# rpi_cm3plus_tablet.net
KiCad netlist of a schematic drawn in EAGLE
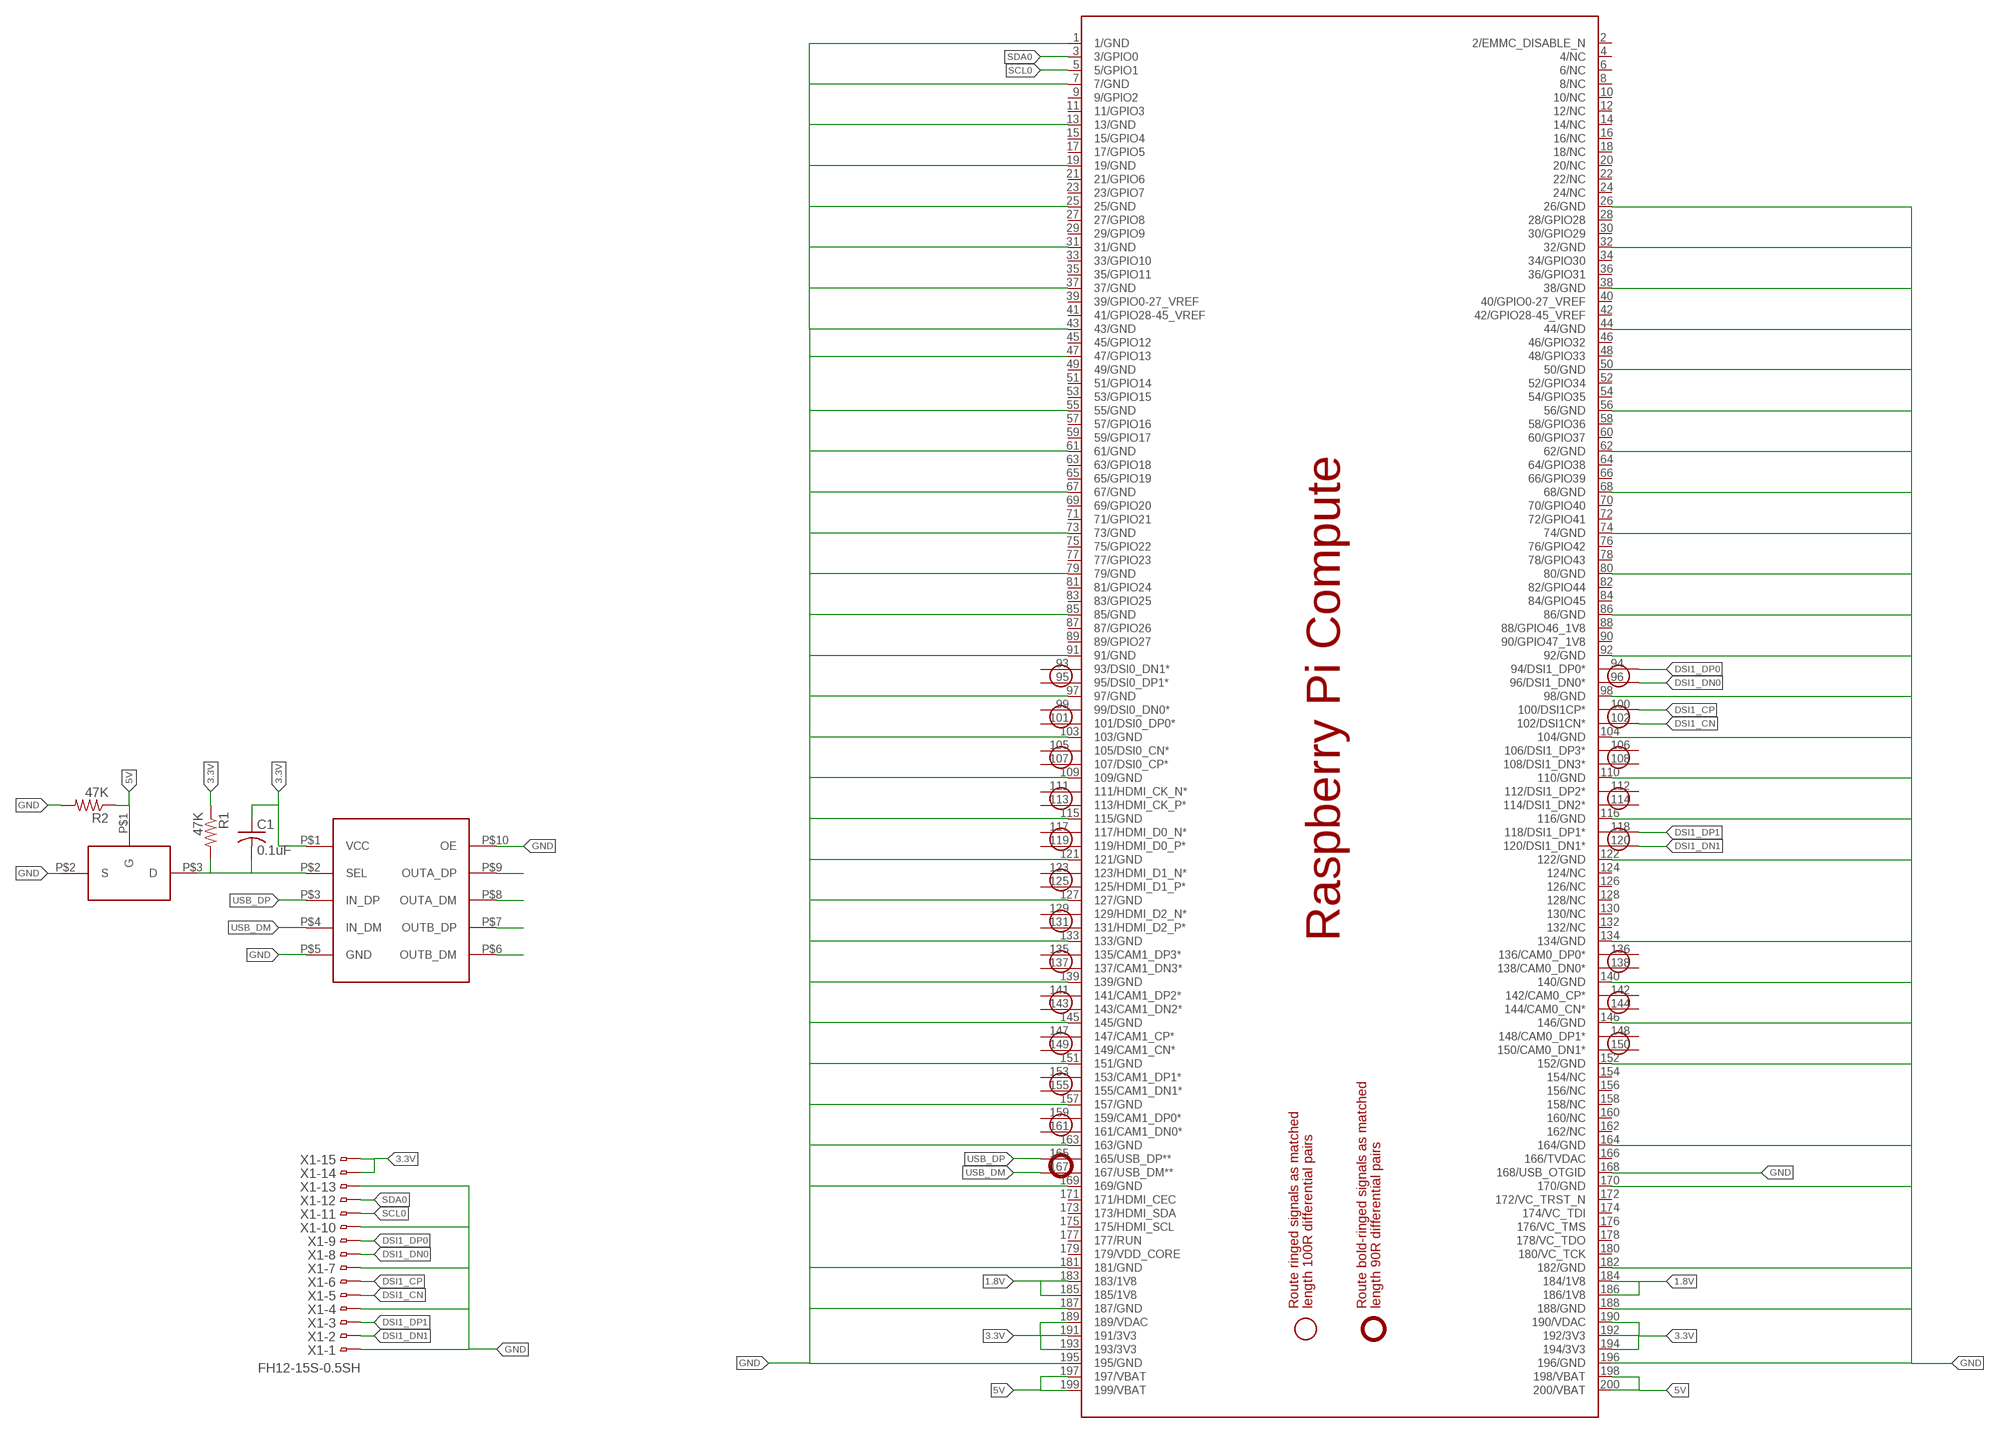
[diagram p0: schematic, sheet 1]

(export (version "E")
  (design (tool "Eeschema 10.0.6"))
  (components
    (comp (ref "C1")
      (value "0.1uF")
      (footprint "eagle-import:C0603K")
      (libsource (lib "eagle-import") (part "C-USC0603K"))
    )
    (comp (ref "PCB1")
      (value "RPI_COMPUTE")
      (footprint "eagle-import:RPI_COMPUTE")
      (libsource (lib "eagle-import") (part "RPI_COMPUTE"))
    )
    (comp (ref "R1")
      (value "47K")
      (footprint "eagle-import:R0603")
      (libsource (lib "eagle-import") (part "R-US_R0603"))
    )
    (comp (ref "R2")
      (value "47K")
      (footprint "eagle-import:R0603")
      (libsource (lib "eagle-import") (part "R-US_R0603"))
    )
    (comp (ref "U$1")
      (value "FSUSB42MUX")
      (footprint "eagle-import:MSOP-10")
      (libsource (lib "eagle-import") (part "FSUSB42MUX"))
    )
    (comp (ref "U$2")
      (value "BSS138N")
      (footprint "eagle-import:SOT-23")
      (libsource (lib "eagle-import") (part "BSS138N"))
    )
    (comp (ref "X1")
      (value "FH12-15S-0.5SH")
      (footprint "eagle-import:FH12-15S-0.5SH")
      (libsource (lib "eagle-import") (part "FH12-15S-0.5SH"))
    )
  )
  (nets
    (net (code "1") (name "1.8V") (class "Default")
      (node (ref "PCB1") (pin "183") (pinfunction "183/1V8_183") (pintype "bidirectional"))
      (node (ref "PCB1") (pin "184") (pinfunction "184/1V8_184") (pintype "bidirectional"))
      (node (ref "PCB1") (pin "185") (pinfunction "185/1V8_185") (pintype "bidirectional"))
      (node (ref "PCB1") (pin "186") (pinfunction "186/1V8_186") (pintype "bidirectional"))
    )
    (net (code "2") (name "3.3V") (class "Default")
      (node (ref "C1") (pin "1") (pinfunction "1_1") (pintype "passive"))
      (node (ref "PCB1") (pin "189") (pinfunction "189/VDAC_189") (pintype "bidirectional"))
      (node (ref "PCB1") (pin "190") (pinfunction "190/VDAC_190") (pintype "bidirectional"))
      (node (ref "PCB1") (pin "191") (pinfunction "191/3V3_191") (pintype "bidirectional"))
      (node (ref "PCB1") (pin "192") (pinfunction "192/3V3_192") (pintype "bidirectional"))
      (node (ref "PCB1") (pin "193") (pinfunction "193/3V3_193") (pintype "bidirectional"))
      (node (ref "PCB1") (pin "194") (pinfunction "194/3V3_194") (pintype "bidirectional"))
      (node (ref "R1") (pin "1") (pinfunction "1_1") (pintype "passive"))
      (node (ref "U$1") (pin "P$1") (pinfunction "VCC_P$1") (pintype "bidirectional"))
      (node (ref "X1") (pin "14") (pinfunction "1_14") (pintype "passive"))
      (node (ref "X1") (pin "15") (pinfunction "1_15") (pintype "passive"))
    )
    (net (code "3") (name "5V") (class "Default")
      (node (ref "PCB1") (pin "197") (pinfunction "197/VBAT_197") (pintype "bidirectional"))
      (node (ref "PCB1") (pin "198") (pinfunction "198/VBAT_198") (pintype "bidirectional"))
      (node (ref "PCB1") (pin "199") (pinfunction "199/VBAT_199") (pintype "bidirectional"))
      (node (ref "PCB1") (pin "200") (pinfunction "200/VBAT_200") (pintype "bidirectional"))
      (node (ref "R2") (pin "1") (pinfunction "1_1") (pintype "passive"))
      (node (ref "U$2") (pin "P$1") (pinfunction "G_P$1") (pintype "bidirectional"))
    )
    (net (code "4") (name "DSI1_CN") (class "Default")
      (node (ref "PCB1") (pin "102") (pinfunction "102/DSI1CN*_102") (pintype "bidirectional"))
      (node (ref "X1") (pin "5") (pinfunction "1_5") (pintype "passive"))
    )
    (net (code "5") (name "DSI1_CP") (class "Default")
      (node (ref "PCB1") (pin "100") (pinfunction "100/DSI1CP*_100") (pintype "bidirectional"))
      (node (ref "X1") (pin "6") (pinfunction "1_6") (pintype "passive"))
    )
    (net (code "6") (name "DSI1_DN0") (class "Default")
      (node (ref "PCB1") (pin "96") (pinfunction "96/DSI1_DN0*_96") (pintype "bidirectional"))
      (node (ref "X1") (pin "8") (pinfunction "1_8") (pintype "passive"))
    )
    (net (code "7") (name "DSI1_DN1") (class "Default")
      (node (ref "PCB1") (pin "120") (pinfunction "120/DSI1_DN1*_120") (pintype "bidirectional"))
      (node (ref "X1") (pin "2") (pinfunction "1_2") (pintype "passive"))
    )
    (net (code "8") (name "DSI1_DP0") (class "Default")
      (node (ref "PCB1") (pin "94") (pinfunction "94/DSI1_DP0*_94") (pintype "bidirectional"))
      (node (ref "X1") (pin "9") (pinfunction "1_9") (pintype "passive"))
    )
    (net (code "9") (name "DSI1_DP1") (class "Default")
      (node (ref "PCB1") (pin "118") (pinfunction "118/DSI1_DP1*_118") (pintype "bidirectional"))
      (node (ref "X1") (pin "3") (pinfunction "1_3") (pintype "passive"))
    )
    (net (code "10") (name "GND") (class "Default")
      (node (ref "PCB1") (pin "1") (pinfunction "1/GND_1") (pintype "bidirectional"))
      (node (ref "PCB1") (pin "103") (pinfunction "103/GND_103") (pintype "bidirectional"))
      (node (ref "PCB1") (pin "104") (pinfunction "104/GND_104") (pintype "bidirectional"))
      (node (ref "PCB1") (pin "109") (pinfunction "109/GND_109") (pintype "bidirectional"))
      (node (ref "PCB1") (pin "110") (pinfunction "110/GND_110") (pintype "bidirectional"))
      (node (ref "PCB1") (pin "115") (pinfunction "115/GND_115") (pintype "bidirectional"))
      (node (ref "PCB1") (pin "116") (pinfunction "116/GND_116") (pintype "bidirectional"))
      (node (ref "PCB1") (pin "121") (pinfunction "121/GND_121") (pintype "bidirectional"))
      (node (ref "PCB1") (pin "122") (pinfunction "122/GND_122") (pintype "bidirectional"))
      (node (ref "PCB1") (pin "127") (pinfunction "127/GND_127") (pintype "bidirectional"))
      (node (ref "PCB1") (pin "13") (pinfunction "13/GND_13") (pintype "bidirectional"))
      (node (ref "PCB1") (pin "133") (pinfunction "133/GND_133") (pintype "bidirectional"))
      (node (ref "PCB1") (pin "134") (pinfunction "134/GND_134") (pintype "bidirectional"))
      (node (ref "PCB1") (pin "139") (pinfunction "139/GND_139") (pintype "bidirectional"))
      (node (ref "PCB1") (pin "140") (pinfunction "140/GND_140") (pintype "bidirectional"))
      (node (ref "PCB1") (pin "145") (pinfunction "145/GND_145") (pintype "bidirectional"))
      (node (ref "PCB1") (pin "146") (pinfunction "146/GND_146") (pintype "bidirectional"))
      (node (ref "PCB1") (pin "151") (pinfunction "151/GND_151") (pintype "bidirectional"))
      (node (ref "PCB1") (pin "152") (pinfunction "152/GND_152") (pintype "bidirectional"))
      (node (ref "PCB1") (pin "157") (pinfunction "157/GND_157") (pintype "bidirectional"))
      (node (ref "PCB1") (pin "163") (pinfunction "163/GND_163") (pintype "bidirectional"))
      (node (ref "PCB1") (pin "164") (pinfunction "164/GND_164") (pintype "bidirectional"))
      (node (ref "PCB1") (pin "168") (pinfunction "168/USB_OTGID_168") (pintype "bidirectional"))
      (node (ref "PCB1") (pin "169") (pinfunction "169/GND_169") (pintype "bidirectional"))
      (node (ref "PCB1") (pin "170") (pinfunction "170/GND_170") (pintype "bidirectional"))
      (node (ref "PCB1") (pin "181") (pinfunction "181/GND_181") (pintype "bidirectional"))
      (node (ref "PCB1") (pin "182") (pinfunction "182/GND_182") (pintype "bidirectional"))
      (node (ref "PCB1") (pin "187") (pinfunction "187/GND_187") (pintype "bidirectional"))
      (node (ref "PCB1") (pin "188") (pinfunction "188/GND_188") (pintype "bidirectional"))
      (node (ref "PCB1") (pin "19") (pinfunction "19/GND_19") (pintype "bidirectional"))
      (node (ref "PCB1") (pin "195") (pinfunction "195/GND_195") (pintype "bidirectional"))
      (node (ref "PCB1") (pin "196") (pinfunction "196/GND_196") (pintype "bidirectional"))
      (node (ref "PCB1") (pin "25") (pinfunction "25/GND_25") (pintype "bidirectional"))
      (node (ref "PCB1") (pin "26") (pinfunction "26/GND_26") (pintype "bidirectional"))
      (node (ref "PCB1") (pin "31") (pinfunction "31/GND_31") (pintype "bidirectional"))
      (node (ref "PCB1") (pin "32") (pinfunction "32/GND_32") (pintype "bidirectional"))
      (node (ref "PCB1") (pin "37") (pinfunction "37/GND_37") (pintype "bidirectional"))
      (node (ref "PCB1") (pin "38") (pinfunction "38/GND_38") (pintype "bidirectional"))
      (node (ref "PCB1") (pin "43") (pinfunction "43/GND_43") (pintype "bidirectional"))
      (node (ref "PCB1") (pin "44") (pinfunction "44/GND_44") (pintype "bidirectional"))
      (node (ref "PCB1") (pin "47") (pinfunction "47/GPIO13_47") (pintype "bidirectional"))
      (node (ref "PCB1") (pin "50") (pinfunction "50/GND_50") (pintype "bidirectional"))
      (node (ref "PCB1") (pin "55") (pinfunction "55/GND_55") (pintype "bidirectional"))
      (node (ref "PCB1") (pin "56") (pinfunction "56/GND_56") (pintype "bidirectional"))
      (node (ref "PCB1") (pin "61") (pinfunction "61/GND_61") (pintype "bidirectional"))
      (node (ref "PCB1") (pin "62") (pinfunction "62/GND_62") (pintype "bidirectional"))
      (node (ref "PCB1") (pin "67") (pinfunction "67/GND_67") (pintype "bidirectional"))
      (node (ref "PCB1") (pin "68") (pinfunction "68/GND_68") (pintype "bidirectional"))
      (node (ref "PCB1") (pin "7") (pinfunction "7/GND_7") (pintype "bidirectional"))
      (node (ref "PCB1") (pin "73") (pinfunction "73/GND_73") (pintype "bidirectional"))
      (node (ref "PCB1") (pin "74") (pinfunction "74/GND_74") (pintype "bidirectional"))
      (node (ref "PCB1") (pin "79") (pinfunction "79/GND_79") (pintype "bidirectional"))
      (node (ref "PCB1") (pin "80") (pinfunction "80/GND_80") (pintype "bidirectional"))
      (node (ref "PCB1") (pin "85") (pinfunction "85/GND_85") (pintype "bidirectional"))
      (node (ref "PCB1") (pin "86") (pinfunction "86/GND_86") (pintype "bidirectional"))
      (node (ref "PCB1") (pin "91") (pinfunction "91/GND_91") (pintype "bidirectional"))
      (node (ref "PCB1") (pin "92") (pinfunction "92/GND_92") (pintype "bidirectional"))
      (node (ref "PCB1") (pin "97") (pinfunction "97/GND_97") (pintype "bidirectional"))
      (node (ref "PCB1") (pin "98") (pinfunction "98/GND_98") (pintype "bidirectional"))
      (node (ref "R2") (pin "2") (pinfunction "2_2") (pintype "passive"))
      (node (ref "U$1") (pin "P$10") (pinfunction "OE_P$10") (pintype "bidirectional"))
      (node (ref "U$1") (pin "P$5") (pinfunction "GND_P$5") (pintype "bidirectional"))
      (node (ref "U$2") (pin "P$2") (pinfunction "S_P$2") (pintype "bidirectional"))
      (node (ref "X1") (pin "1") (pinfunction "1_1") (pintype "passive"))
      (node (ref "X1") (pin "10") (pinfunction "1_10") (pintype "passive"))
      (node (ref "X1") (pin "13") (pinfunction "1_13") (pintype "passive"))
      (node (ref "X1") (pin "4") (pinfunction "1_4") (pintype "passive"))
      (node (ref "X1") (pin "7") (pinfunction "1_7") (pintype "passive"))
    )
    (net (code "11") (name "Net-(U$1-SEL)") (class "Default")
      (node (ref "C1") (pin "2") (pinfunction "2_2") (pintype "passive"))
      (node (ref "R1") (pin "2") (pinfunction "2_2") (pintype "passive"))
      (node (ref "U$1") (pin "P$2") (pinfunction "SEL_P$2") (pintype "bidirectional"))
      (node (ref "U$2") (pin "P$3") (pinfunction "D_P$3") (pintype "bidirectional"))
    )
    (net (code "12") (name "SCL0") (class "Default")
      (node (ref "PCB1") (pin "5") (pinfunction "5/GPIO1_5") (pintype "bidirectional"))
      (node (ref "X1") (pin "11") (pinfunction "1_11") (pintype "passive"))
    )
    (net (code "13") (name "SDA0") (class "Default")
      (node (ref "PCB1") (pin "3") (pinfunction "3/GPIO0_3") (pintype "bidirectional"))
      (node (ref "X1") (pin "12") (pinfunction "1_12") (pintype "passive"))
    )
    (net (code "14") (name "USB_DM") (class "Default")
      (node (ref "PCB1") (pin "167") (pinfunction "167/USB_DM**_167") (pintype "bidirectional"))
      (node (ref "U$1") (pin "P$4") (pinfunction "IN_DM_P$4") (pintype "bidirectional"))
    )
    (net (code "15") (name "USB_DP") (class "Default")
      (node (ref "PCB1") (pin "165") (pinfunction "165/USB_DP**_165") (pintype "bidirectional"))
      (node (ref "U$1") (pin "P$3") (pinfunction "IN_DP_P$3") (pintype "bidirectional"))
    )
    (net (code "16") (name "unconnected-(PCB1-2{slash}EMMC_DISABLE_N-Pad2)") (class "Default")
      (node (ref "PCB1") (pin "2") (pinfunction "2/EMMC_DISABLE_N_2") (pintype "bidirectional"))
    )
    (net (code "17") (name "unconnected-(PCB1-4{slash}NC-Pad4)") (class "Default")
      (node (ref "PCB1") (pin "4") (pinfunction "4/NC_4") (pintype "bidirectional"))
    )
    (net (code "18") (name "unconnected-(PCB1-6{slash}NC-Pad6)") (class "Default")
      (node (ref "PCB1") (pin "6") (pinfunction "6/NC_6") (pintype "bidirectional"))
    )
    (net (code "19") (name "unconnected-(PCB1-8{slash}NC-Pad8)") (class "Default")
      (node (ref "PCB1") (pin "8") (pinfunction "8/NC_8") (pintype "bidirectional"))
    )
    (net (code "20") (name "unconnected-(PCB1-9{slash}GPIO2-Pad9)") (class "Default")
      (node (ref "PCB1") (pin "9") (pinfunction "9/GPIO2_9") (pintype "bidirectional"))
    )
    (net (code "21") (name "unconnected-(PCB1-10{slash}NC-Pad10)") (class "Default")
      (node (ref "PCB1") (pin "10") (pinfunction "10/NC_10") (pintype "bidirectional"))
    )
    (net (code "22") (name "unconnected-(PCB1-11{slash}GPIO3-Pad11)") (class "Default")
      (node (ref "PCB1") (pin "11") (pinfunction "11/GPIO3_11") (pintype "bidirectional"))
    )
    (net (code "23") (name "unconnected-(PCB1-12{slash}NC-Pad12)") (class "Default")
      (node (ref "PCB1") (pin "12") (pinfunction "12/NC_12") (pintype "bidirectional"))
    )
    (net (code "24") (name "unconnected-(PCB1-14{slash}NC-Pad14)") (class "Default")
      (node (ref "PCB1") (pin "14") (pinfunction "14/NC_14") (pintype "bidirectional"))
    )
    (net (code "25") (name "unconnected-(PCB1-15{slash}GPIO4-Pad15)") (class "Default")
      (node (ref "PCB1") (pin "15") (pinfunction "15/GPIO4_15") (pintype "bidirectional"))
    )
    (net (code "26") (name "unconnected-(PCB1-16{slash}NC-Pad16)") (class "Default")
      (node (ref "PCB1") (pin "16") (pinfunction "16/NC_16") (pintype "bidirectional"))
    )
    (net (code "27") (name "unconnected-(PCB1-17{slash}GPIO5-Pad17)") (class "Default")
      (node (ref "PCB1") (pin "17") (pinfunction "17/GPIO5_17") (pintype "bidirectional"))
    )
    (net (code "28") (name "unconnected-(PCB1-18{slash}NC-Pad18)") (class "Default")
      (node (ref "PCB1") (pin "18") (pinfunction "18/NC_18") (pintype "bidirectional"))
    )
    (net (code "29") (name "unconnected-(PCB1-20{slash}NC-Pad20)") (class "Default")
      (node (ref "PCB1") (pin "20") (pinfunction "20/NC_20") (pintype "bidirectional"))
    )
    (net (code "30") (name "unconnected-(PCB1-21{slash}GPIO6-Pad21)") (class "Default")
      (node (ref "PCB1") (pin "21") (pinfunction "21/GPIO6_21") (pintype "bidirectional"))
    )
    (net (code "31") (name "unconnected-(PCB1-22{slash}NC-Pad22)") (class "Default")
      (node (ref "PCB1") (pin "22") (pinfunction "22/NC_22") (pintype "bidirectional"))
    )
    (net (code "32") (name "unconnected-(PCB1-23{slash}GPIO7-Pad23)") (class "Default")
      (node (ref "PCB1") (pin "23") (pinfunction "23/GPIO7_23") (pintype "bidirectional"))
    )
    (net (code "33") (name "unconnected-(PCB1-24{slash}NC-Pad24)") (class "Default")
      (node (ref "PCB1") (pin "24") (pinfunction "24/NC_24") (pintype "bidirectional"))
    )
    (net (code "34") (name "unconnected-(PCB1-27{slash}GPIO8-Pad27)") (class "Default")
      (node (ref "PCB1") (pin "27") (pinfunction "27/GPIO8_27") (pintype "bidirectional"))
    )
    (net (code "35") (name "unconnected-(PCB1-28{slash}GPIO28-Pad28)") (class "Default")
      (node (ref "PCB1") (pin "28") (pinfunction "28/GPIO28_28") (pintype "bidirectional"))
    )
    (net (code "36") (name "unconnected-(PCB1-29{slash}GPIO9-Pad29)") (class "Default")
      (node (ref "PCB1") (pin "29") (pinfunction "29/GPIO9_29") (pintype "bidirectional"))
    )
    (net (code "37") (name "unconnected-(PCB1-30{slash}GPIO29-Pad30)") (class "Default")
      (node (ref "PCB1") (pin "30") (pinfunction "30/GPIO29_30") (pintype "bidirectional"))
    )
    (net (code "38") (name "unconnected-(PCB1-33{slash}GPIO10-Pad33)") (class "Default")
      (node (ref "PCB1") (pin "33") (pinfunction "33/GPIO10_33") (pintype "bidirectional"))
    )
    (net (code "39") (name "unconnected-(PCB1-34{slash}GPIO30-Pad34)") (class "Default")
      (node (ref "PCB1") (pin "34") (pinfunction "34/GPIO30_34") (pintype "bidirectional"))
    )
    (net (code "40") (name "unconnected-(PCB1-35{slash}GPIO11-Pad35)") (class "Default")
      (node (ref "PCB1") (pin "35") (pinfunction "35/GPIO11_35") (pintype "bidirectional"))
    )
    (net (code "41") (name "unconnected-(PCB1-36{slash}GPIO31-Pad36)") (class "Default")
      (node (ref "PCB1") (pin "36") (pinfunction "36/GPIO31_36") (pintype "bidirectional"))
    )
    (net (code "42") (name "unconnected-(PCB1-39{slash}GPIO0-27_VREF-Pad39)") (class "Default")
      (node (ref "PCB1") (pin "39") (pinfunction "39/GPIO0-27_VREF_39") (pintype "bidirectional"))
    )
    (net (code "43") (name "unconnected-(PCB1-40{slash}GPIO0-27_VREF-Pad40)") (class "Default")
      (node (ref "PCB1") (pin "40") (pinfunction "40/GPIO0-27_VREF_40") (pintype "bidirectional"))
    )
    (net (code "44") (name "unconnected-(PCB1-41{slash}GPIO28-45_VREF-Pad41)") (class "Default")
      (node (ref "PCB1") (pin "41") (pinfunction "41/GPIO28-45_VREF_41") (pintype "bidirectional"))
    )
    (net (code "45") (name "unconnected-(PCB1-42{slash}GPIO28-45_VREF-Pad42)") (class "Default")
      (node (ref "PCB1") (pin "42") (pinfunction "42/GPIO28-45_VREF_42") (pintype "bidirectional"))
    )
    (net (code "46") (name "unconnected-(PCB1-45{slash}GPIO12-Pad45)") (class "Default")
      (node (ref "PCB1") (pin "45") (pinfunction "45/GPIO12_45") (pintype "bidirectional"))
    )
    (net (code "47") (name "unconnected-(PCB1-46{slash}GPIO32-Pad46)") (class "Default")
      (node (ref "PCB1") (pin "46") (pinfunction "46/GPIO32_46") (pintype "bidirectional"))
    )
    (net (code "48") (name "unconnected-(PCB1-48{slash}GPIO33-Pad48)") (class "Default")
      (node (ref "PCB1") (pin "48") (pinfunction "48/GPIO33_48") (pintype "bidirectional"))
    )
    (net (code "49") (name "unconnected-(PCB1-49{slash}GND-Pad49)") (class "Default")
      (node (ref "PCB1") (pin "49") (pinfunction "49/GND_49") (pintype "bidirectional"))
    )
    (net (code "50") (name "unconnected-(PCB1-51{slash}GPIO14-Pad51)") (class "Default")
      (node (ref "PCB1") (pin "51") (pinfunction "51/GPIO14_51") (pintype "bidirectional"))
    )
    (net (code "51") (name "unconnected-(PCB1-52{slash}GPIO34-Pad52)") (class "Default")
      (node (ref "PCB1") (pin "52") (pinfunction "52/GPIO34_52") (pintype "bidirectional"))
    )
    (net (code "52") (name "unconnected-(PCB1-53{slash}GPIO15-Pad53)") (class "Default")
      (node (ref "PCB1") (pin "53") (pinfunction "53/GPIO15_53") (pintype "bidirectional"))
    )
    (net (code "53") (name "unconnected-(PCB1-54{slash}GPIO35-Pad54)") (class "Default")
      (node (ref "PCB1") (pin "54") (pinfunction "54/GPIO35_54") (pintype "bidirectional"))
    )
    (net (code "54") (name "unconnected-(PCB1-57{slash}GPIO16-Pad57)") (class "Default")
      (node (ref "PCB1") (pin "57") (pinfunction "57/GPIO16_57") (pintype "bidirectional"))
    )
    (net (code "55") (name "unconnected-(PCB1-58{slash}GPIO36-Pad58)") (class "Default")
      (node (ref "PCB1") (pin "58") (pinfunction "58/GPIO36_58") (pintype "bidirectional"))
    )
    (net (code "56") (name "unconnected-(PCB1-59{slash}GPIO17-Pad59)") (class "Default")
      (node (ref "PCB1") (pin "59") (pinfunction "59/GPIO17_59") (pintype "bidirectional"))
    )
    (net (code "57") (name "unconnected-(PCB1-60{slash}GPIO37-Pad60)") (class "Default")
      (node (ref "PCB1") (pin "60") (pinfunction "60/GPIO37_60") (pintype "bidirectional"))
    )
    (net (code "58") (name "unconnected-(PCB1-63{slash}GPIO18-Pad63)") (class "Default")
      (node (ref "PCB1") (pin "63") (pinfunction "63/GPIO18_63") (pintype "bidirectional"))
    )
    (net (code "59") (name "unconnected-(PCB1-64{slash}GPIO38-Pad64)") (class "Default")
      (node (ref "PCB1") (pin "64") (pinfunction "64/GPIO38_64") (pintype "bidirectional"))
    )
    (net (code "60") (name "unconnected-(PCB1-65{slash}GPIO19-Pad65)") (class "Default")
      (node (ref "PCB1") (pin "65") (pinfunction "65/GPIO19_65") (pintype "bidirectional"))
    )
    (net (code "61") (name "unconnected-(PCB1-66{slash}GPIO39-Pad66)") (class "Default")
      (node (ref "PCB1") (pin "66") (pinfunction "66/GPIO39_66") (pintype "bidirectional"))
    )
    (net (code "62") (name "unconnected-(PCB1-69{slash}GPIO20-Pad69)") (class "Default")
      (node (ref "PCB1") (pin "69") (pinfunction "69/GPIO20_69") (pintype "bidirectional"))
    )
    (net (code "63") (name "unconnected-(PCB1-70{slash}GPIO40-Pad70)") (class "Default")
      (node (ref "PCB1") (pin "70") (pinfunction "70/GPIO40_70") (pintype "bidirectional"))
    )
    (net (code "64") (name "unconnected-(PCB1-71{slash}GPIO21-Pad71)") (class "Default")
      (node (ref "PCB1") (pin "71") (pinfunction "71/GPIO21_71") (pintype "bidirectional"))
    )
    (net (code "65") (name "unconnected-(PCB1-72{slash}GPIO41-Pad72)") (class "Default")
      (node (ref "PCB1") (pin "72") (pinfunction "72/GPIO41_72") (pintype "bidirectional"))
    )
    (net (code "66") (name "unconnected-(PCB1-75{slash}GPIO22-Pad75)") (class "Default")
      (node (ref "PCB1") (pin "75") (pinfunction "75/GPIO22_75") (pintype "bidirectional"))
    )
    (net (code "67") (name "unconnected-(PCB1-76{slash}GPIO42-Pad76)") (class "Default")
      (node (ref "PCB1") (pin "76") (pinfunction "76/GPIO42_76") (pintype "bidirectional"))
    )
    (net (code "68") (name "unconnected-(PCB1-77{slash}GPIO23-Pad77)") (class "Default")
      (node (ref "PCB1") (pin "77") (pinfunction "77/GPIO23_77") (pintype "bidirectional"))
    )
    (net (code "69") (name "unconnected-(PCB1-78{slash}GPIO43-Pad78)") (class "Default")
      (node (ref "PCB1") (pin "78") (pinfunction "78/GPIO43_78") (pintype "bidirectional"))
    )
    (net (code "70") (name "unconnected-(PCB1-81{slash}GPIO24-Pad81)") (class "Default")
      (node (ref "PCB1") (pin "81") (pinfunction "81/GPIO24_81") (pintype "bidirectional"))
    )
    (net (code "71") (name "unconnected-(PCB1-82{slash}GPIO44-Pad82)") (class "Default")
      (node (ref "PCB1") (pin "82") (pinfunction "82/GPIO44_82") (pintype "bidirectional"))
    )
    (net (code "72") (name "unconnected-(PCB1-83{slash}GPIO25-Pad83)") (class "Default")
      (node (ref "PCB1") (pin "83") (pinfunction "83/GPIO25_83") (pintype "bidirectional"))
    )
    (net (code "73") (name "unconnected-(PCB1-84{slash}GPIO45-Pad84)") (class "Default")
      (node (ref "PCB1") (pin "84") (pinfunction "84/GPIO45_84") (pintype "bidirectional"))
    )
    (net (code "74") (name "unconnected-(PCB1-87{slash}GPIO26-Pad87)") (class "Default")
      (node (ref "PCB1") (pin "87") (pinfunction "87/GPIO26_87") (pintype "bidirectional"))
    )
    (net (code "75") (name "unconnected-(PCB1-88{slash}GPIO46_1V8-Pad88)") (class "Default")
      (node (ref "PCB1") (pin "88") (pinfunction "88/GPIO46_1V8_88") (pintype "bidirectional"))
    )
    (net (code "76") (name "unconnected-(PCB1-89{slash}GPIO27-Pad89)") (class "Default")
      (node (ref "PCB1") (pin "89") (pinfunction "89/GPIO27_89") (pintype "bidirectional"))
    )
    (net (code "77") (name "unconnected-(PCB1-90{slash}GPIO47_1V8-Pad90)") (class "Default")
      (node (ref "PCB1") (pin "90") (pinfunction "90/GPIO47_1V8_90") (pintype "bidirectional"))
    )
    (net (code "78") (name "unconnected-(PCB1-93{slash}DSI0_DN1*-Pad93)") (class "Default")
      (node (ref "PCB1") (pin "93") (pinfunction "93/DSI0_DN1*_93") (pintype "bidirectional"))
    )
    (net (code "79") (name "unconnected-(PCB1-95{slash}DSI0_DP1*-Pad95)") (class "Default")
      (node (ref "PCB1") (pin "95") (pinfunction "95/DSI0_DP1*_95") (pintype "bidirectional"))
    )
    (net (code "80") (name "unconnected-(PCB1-99{slash}DSI0_DN0*-Pad99)") (class "Default")
      (node (ref "PCB1") (pin "99") (pinfunction "99/DSI0_DN0*_99") (pintype "bidirectional"))
    )
    (net (code "81") (name "unconnected-(PCB1-101{slash}DSI0_DP0*-Pad101)") (class "Default")
      (node (ref "PCB1") (pin "101") (pinfunction "101/DSI0_DP0*_101") (pintype "bidirectional"))
    )
    (net (code "82") (name "unconnected-(PCB1-105{slash}DSI0_CN*-Pad105)") (class "Default")
      (node (ref "PCB1") (pin "105") (pinfunction "105/DSI0_CN*_105") (pintype "bidirectional"))
    )
    (net (code "83") (name "unconnected-(PCB1-106{slash}DSI1_DP3*-Pad106)") (class "Default")
      (node (ref "PCB1") (pin "106") (pinfunction "106/DSI1_DP3*_106") (pintype "bidirectional"))
    )
    (net (code "84") (name "unconnected-(PCB1-107{slash}DSI0_CP*-Pad107)") (class "Default")
      (node (ref "PCB1") (pin "107") (pinfunction "107/DSI0_CP*_107") (pintype "bidirectional"))
    )
    (net (code "85") (name "unconnected-(PCB1-108{slash}DSI1_DN3*-Pad108)") (class "Default")
      (node (ref "PCB1") (pin "108") (pinfunction "108/DSI1_DN3*_108") (pintype "bidirectional"))
    )
    (net (code "86") (name "unconnected-(PCB1-111{slash}HDMI_CK_N*-Pad111)") (class "Default")
      (node (ref "PCB1") (pin "111") (pinfunction "111/HDMI_CK_N*_111") (pintype "bidirectional"))
    )
    (net (code "87") (name "unconnected-(PCB1-112{slash}DSI1_DP2*-Pad112)") (class "Default")
      (node (ref "PCB1") (pin "112") (pinfunction "112/DSI1_DP2*_112") (pintype "bidirectional"))
    )
    (net (code "88") (name "unconnected-(PCB1-113{slash}HDMI_CK_P*-Pad113)") (class "Default")
      (node (ref "PCB1") (pin "113") (pinfunction "113/HDMI_CK_P*_113") (pintype "bidirectional"))
    )
    (net (code "89") (name "unconnected-(PCB1-114{slash}DSI1_DN2*-Pad114)") (class "Default")
      (node (ref "PCB1") (pin "114") (pinfunction "114/DSI1_DN2*_114") (pintype "bidirectional"))
    )
    (net (code "90") (name "unconnected-(PCB1-117{slash}HDMI_D0_N*-Pad117)") (class "Default")
      (node (ref "PCB1") (pin "117") (pinfunction "117/HDMI_D0_N*_117") (pintype "bidirectional"))
    )
    (net (code "91") (name "unconnected-(PCB1-119{slash}HDMI_D0_P*-Pad119)") (class "Default")
      (node (ref "PCB1") (pin "119") (pinfunction "119/HDMI_D0_P*_119") (pintype "bidirectional"))
    )
    (net (code "92") (name "unconnected-(PCB1-123{slash}HDMI_D1_N*-Pad123)") (class "Default")
      (node (ref "PCB1") (pin "123") (pinfunction "123/HDMI_D1_N*_123") (pintype "bidirectional"))
    )
    (net (code "93") (name "unconnected-(PCB1-124{slash}NC-Pad124)") (class "Default")
      (node (ref "PCB1") (pin "124") (pinfunction "124/NC_124") (pintype "bidirectional"))
    )
    (net (code "94") (name "unconnected-(PCB1-125{slash}HDMI_D1_P*-Pad125)") (class "Default")
      (node (ref "PCB1") (pin "125") (pinfunction "125/HDMI_D1_P*_125") (pintype "bidirectional"))
    )
    (net (code "95") (name "unconnected-(PCB1-126{slash}NC-Pad126)") (class "Default")
      (node (ref "PCB1") (pin "126") (pinfunction "126/NC_126") (pintype "bidirectional"))
    )
    (net (code "96") (name "unconnected-(PCB1-128{slash}NC-Pad128)") (class "Default")
      (node (ref "PCB1") (pin "128") (pinfunction "128/NC_128") (pintype "bidirectional"))
    )
    (net (code "97") (name "unconnected-(PCB1-129{slash}HDMI_D2_N*-Pad129)") (class "Default")
      (node (ref "PCB1") (pin "129") (pinfunction "129/HDMI_D2_N*_129") (pintype "bidirectional"))
    )
    (net (code "98") (name "unconnected-(PCB1-130{slash}NC-Pad130)") (class "Default")
      (node (ref "PCB1") (pin "130") (pinfunction "130/NC_130") (pintype "bidirectional"))
    )
    (net (code "99") (name "unconnected-(PCB1-131{slash}HDMI_D2_P*-Pad131)") (class "Default")
      (node (ref "PCB1") (pin "131") (pinfunction "131/HDMI_D2_P*_131") (pintype "bidirectional"))
    )
    (net (code "100") (name "unconnected-(PCB1-132{slash}NC-Pad132)") (class "Default")
      (node (ref "PCB1") (pin "132") (pinfunction "132/NC_132") (pintype "bidirectional"))
    )
    (net (code "101") (name "unconnected-(PCB1-135{slash}CAM1_DP3*-Pad135)") (class "Default")
      (node (ref "PCB1") (pin "135") (pinfunction "135/CAM1_DP3*_135") (pintype "bidirectional"))
    )
    (net (code "102") (name "unconnected-(PCB1-136{slash}CAM0_DP0*-Pad136)") (class "Default")
      (node (ref "PCB1") (pin "136") (pinfunction "136/CAM0_DP0*_136") (pintype "bidirectional"))
    )
    (net (code "103") (name "unconnected-(PCB1-137{slash}CAM1_DN3*-Pad137)") (class "Default")
      (node (ref "PCB1") (pin "137") (pinfunction "137/CAM1_DN3*_137") (pintype "bidirectional"))
    )
    (net (code "104") (name "unconnected-(PCB1-138{slash}CAM0_DN0*-Pad138)") (class "Default")
      (node (ref "PCB1") (pin "138") (pinfunction "138/CAM0_DN0*_138") (pintype "bidirectional"))
    )
    (net (code "105") (name "unconnected-(PCB1-141{slash}CAM1_DP2*-Pad141)") (class "Default")
      (node (ref "PCB1") (pin "141") (pinfunction "141/CAM1_DP2*_141") (pintype "bidirectional"))
    )
    (net (code "106") (name "unconnected-(PCB1-142{slash}CAM0_CP*-Pad142)") (class "Default")
      (node (ref "PCB1") (pin "142") (pinfunction "142/CAM0_CP*_142") (pintype "bidirectional"))
    )
    (net (code "107") (name "unconnected-(PCB1-143{slash}CAM1_DN2*-Pad143)") (class "Default")
      (node (ref "PCB1") (pin "143") (pinfunction "143/CAM1_DN2*_143") (pintype "bidirectional"))
    )
    (net (code "108") (name "unconnected-(PCB1-144{slash}CAM0_CN*-Pad144)") (class "Default")
      (node (ref "PCB1") (pin "144") (pinfunction "144/CAM0_CN*_144") (pintype "bidirectional"))
    )
    (net (code "109") (name "unconnected-(PCB1-147{slash}CAM1_CP*-Pad147)") (class "Default")
      (node (ref "PCB1") (pin "147") (pinfunction "147/CAM1_CP*_147") (pintype "bidirectional"))
    )
    (net (code "110") (name "unconnected-(PCB1-148{slash}CAM0_DP1*-Pad148)") (class "Default")
      (node (ref "PCB1") (pin "148") (pinfunction "148/CAM0_DP1*_148") (pintype "bidirectional"))
    )
    (net (code "111") (name "unconnected-(PCB1-149{slash}CAM1_CN*-Pad149)") (class "Default")
      (node (ref "PCB1") (pin "149") (pinfunction "149/CAM1_CN*_149") (pintype "bidirectional"))
    )
    (net (code "112") (name "unconnected-(PCB1-150{slash}CAM0_DN1*-Pad150)") (class "Default")
      (node (ref "PCB1") (pin "150") (pinfunction "150/CAM0_DN1*_150") (pintype "bidirectional"))
    )
    (net (code "113") (name "unconnected-(PCB1-153{slash}CAM1_DP1*-Pad153)") (class "Default")
      (node (ref "PCB1") (pin "153") (pinfunction "153/CAM1_DP1*_153") (pintype "bidirectional"))
    )
    (net (code "114") (name "unconnected-(PCB1-154{slash}NC-Pad154)") (class "Default")
      (node (ref "PCB1") (pin "154") (pinfunction "154/NC_154") (pintype "bidirectional"))
    )
    (net (code "115") (name "unconnected-(PCB1-155{slash}CAM1_DN1*-Pad155)") (class "Default")
      (node (ref "PCB1") (pin "155") (pinfunction "155/CAM1_DN1*_155") (pintype "bidirectional"))
    )
    (net (code "116") (name "unconnected-(PCB1-156{slash}NC-Pad156)") (class "Default")
      (node (ref "PCB1") (pin "156") (pinfunction "156/NC_156") (pintype "bidirectional"))
    )
    (net (code "117") (name "unconnected-(PCB1-158{slash}NC-Pad158)") (class "Default")
      (node (ref "PCB1") (pin "158") (pinfunction "158/NC_158") (pintype "bidirectional"))
    )
    (net (code "118") (name "unconnected-(PCB1-159{slash}CAM1_DP0*-Pad159)") (class "Default")
      (node (ref "PCB1") (pin "159") (pinfunction "159/CAM1_DP0*_159") (pintype "bidirectional"))
    )
    (net (code "119") (name "unconnected-(PCB1-160{slash}NC-Pad160)") (class "Default")
      (node (ref "PCB1") (pin "160") (pinfunction "160/NC_160") (pintype "bidirectional"))
    )
    (net (code "120") (name "unconnected-(PCB1-161{slash}CAM1_DN0*-Pad161)") (class "Default")
      (node (ref "PCB1") (pin "161") (pinfunction "161/CAM1_DN0*_161") (pintype "bidirectional"))
    )
    (net (code "121") (name "unconnected-(PCB1-162{slash}NC-Pad162)") (class "Default")
      (node (ref "PCB1") (pin "162") (pinfunction "162/NC_162") (pintype "bidirectional"))
    )
    (net (code "122") (name "unconnected-(PCB1-166{slash}TVDAC-Pad166)") (class "Default")
      (node (ref "PCB1") (pin "166") (pinfunction "166/TVDAC_166") (pintype "bidirectional"))
    )
    (net (code "123") (name "unconnected-(PCB1-171{slash}HDMI_CEC-Pad171)") (class "Default")
      (node (ref "PCB1") (pin "171") (pinfunction "171/HDMI_CEC_171") (pintype "bidirectional"))
    )
    (net (code "124") (name "unconnected-(PCB1-172{slash}VC_TRST_N-Pad172)") (class "Default")
      (node (ref "PCB1") (pin "172") (pinfunction "172/VC_TRST_N_172") (pintype "bidirectional"))
    )
    (net (code "125") (name "unconnected-(PCB1-173{slash}HDMI_SDA-Pad173)") (class "Default")
      (node (ref "PCB1") (pin "173") (pinfunction "173/HDMI_SDA_173") (pintype "bidirectional"))
    )
    (net (code "126") (name "unconnected-(PCB1-174{slash}VC_TDI-Pad174)") (class "Default")
      (node (ref "PCB1") (pin "174") (pinfunction "174/VC_TDI_174") (pintype "bidirectional"))
    )
    (net (code "127") (name "unconnected-(PCB1-175{slash}HDMI_SCL-Pad175)") (class "Default")
      (node (ref "PCB1") (pin "175") (pinfunction "175/HDMI_SCL_175") (pintype "bidirectional"))
    )
    (net (code "128") (name "unconnected-(PCB1-176{slash}VC_TMS-Pad176)") (class "Default")
      (node (ref "PCB1") (pin "176") (pinfunction "176/VC_TMS_176") (pintype "bidirectional"))
    )
    (net (code "129") (name "unconnected-(PCB1-177{slash}RUN-Pad177)") (class "Default")
      (node (ref "PCB1") (pin "177") (pinfunction "177/RUN_177") (pintype "bidirectional"))
    )
    (net (code "130") (name "unconnected-(PCB1-178{slash}VC_TDO-Pad178)") (class "Default")
      (node (ref "PCB1") (pin "178") (pinfunction "178/VC_TDO_178") (pintype "bidirectional"))
    )
    (net (code "131") (name "unconnected-(PCB1-179{slash}VDD_CORE-Pad179)") (class "Default")
      (node (ref "PCB1") (pin "179") (pinfunction "179/VDD_CORE_179") (pintype "bidirectional"))
    )
    (net (code "132") (name "unconnected-(PCB1-180{slash}VC_TCK-Pad180)") (class "Default")
      (node (ref "PCB1") (pin "180") (pinfunction "180/VC_TCK_180") (pintype "bidirectional"))
    )
    (net (code "133") (name "unconnected-(U$1-OUTA_DM-PadP$8)") (class "Default")
      (node (ref "U$1") (pin "P$8") (pinfunction "OUTA_DM_P$8") (pintype "bidirectional"))
    )
    (net (code "134") (name "unconnected-(U$1-OUTA_DP-PadP$9)") (class "Default")
      (node (ref "U$1") (pin "P$9") (pinfunction "OUTA_DP_P$9") (pintype "bidirectional"))
    )
    (net (code "135") (name "unconnected-(U$1-OUTB_DM-PadP$6)") (class "Default")
      (node (ref "U$1") (pin "P$6") (pinfunction "OUTB_DM_P$6") (pintype "bidirectional"))
    )
    (net (code "136") (name "unconnected-(U$1-OUTB_DP-PadP$7)") (class "Default")
      (node (ref "U$1") (pin "P$7") (pinfunction "OUTB_DP_P$7") (pintype "bidirectional"))
    )
  )
)
